# ESP32_BLE.net
KiCad netlist of a schematic drawn in Altium Designer
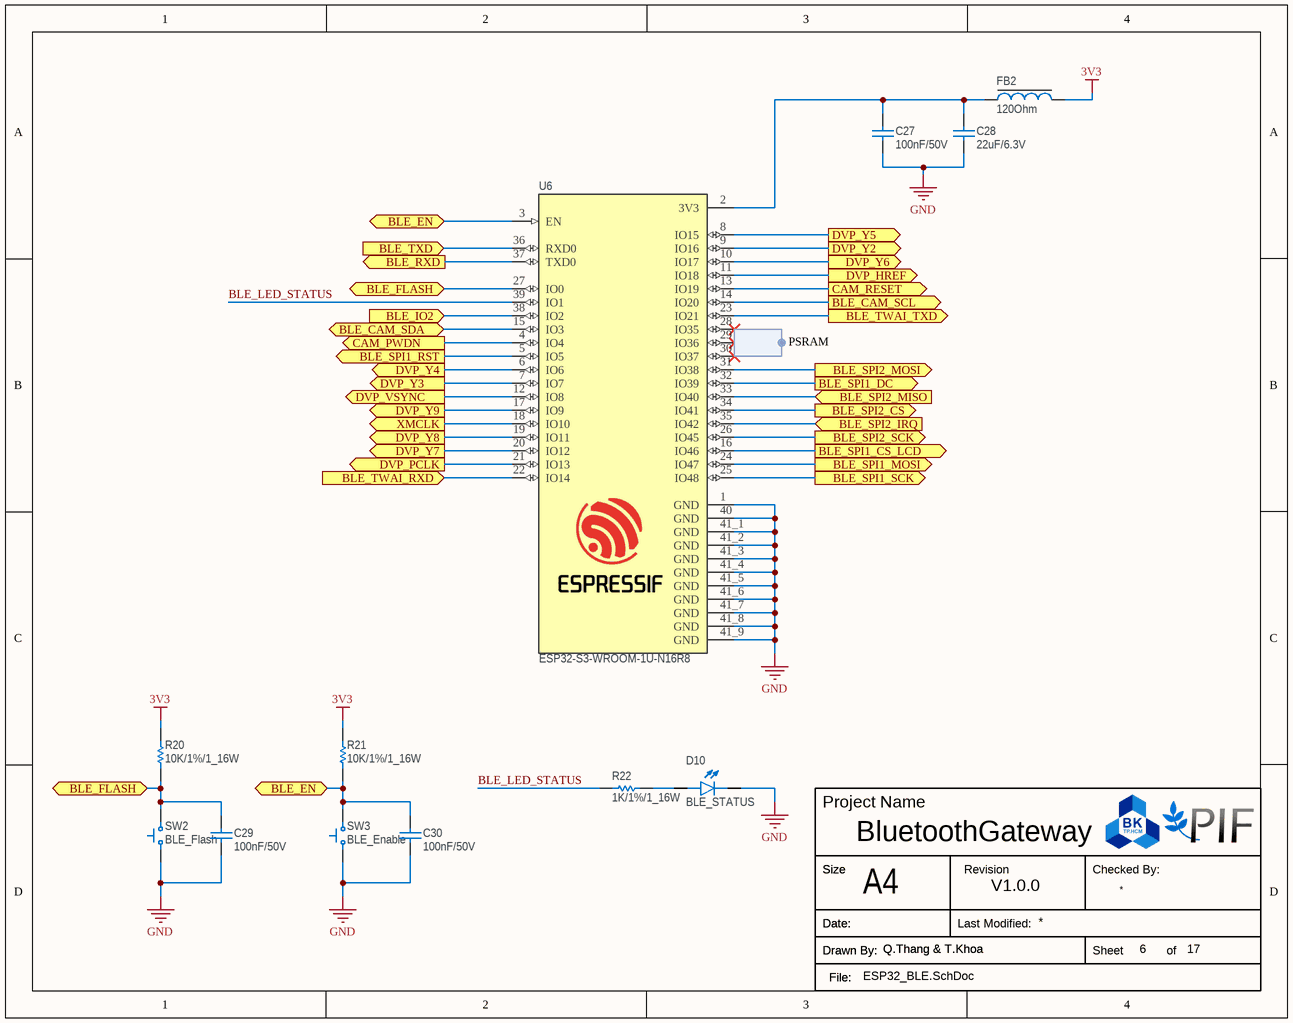
[diagram p0: ESP32_BLE.SchDoc]

(export (version "E")
  (design (tool "Eeschema 10.0.6"))
  (components
    (comp (ref "C27")
      (value "100nF/50V")
      (footprint "CAP_0805")
      (description "CAP, size 0805, 100nF, 50V")
      (fields (field (name "SUPPLY PART NUMBER") "Tụ Gốm 0805 100nF (0.1uF) 50V"))
      (libsource (lib "BluetoothTracking") (part "Ceramic_Cap_100nF_50V_0805"))
    )
    (comp (ref "C28")
      (value "22uF/6.3V")
      (footprint "CAP_0805")
      (description "CAP, size 0805, 22uF, 6.3V")
      (fields (field (name "SUPPLY PART NUMBER") "Tụ Gốm 0805 22uF 6.3V"))
      (libsource (lib "BluetoothTracking") (part "Ceramic_Cap_22uF_6.3V_0805"))
    )
    (comp (ref "C29")
      (value "100nF/50V")
      (footprint "CAP_0402")
      (description "CAP, size 0402, 100nF, 50V")
      (fields (field (name "SUPPLY PART NUMBER") "Tụ Gốm 0402 100nF (0.1uF) 50V"))
      (libsource (lib "BluetoothTracking") (part "Ceramic_Cap_100nF_50V_0402"))
    )
    (comp (ref "C30")
      (value "100nF/50V")
      (footprint "CAP_0402")
      (description "CAP, size 0402, 100nF, 50V")
      (fields (field (name "SUPPLY PART NUMBER") "Tụ Gốm 0402 100nF (0.1uF) 50V"))
      (libsource (lib "BluetoothTracking") (part "Ceramic_Cap_100nF_50V_0402"))
    )
    (comp (ref "D10")
      (value "BLE_STATUS")
      (footprint "LED_0603Y")
      (description "LED Yellow 0603")
      (fields (field (name "SUPPLY PART NUMBER") "LED Vàng 0603 Dán SMD Trong Suốt Harvatek"))
      (libsource (lib "BluetoothTracking") (part "LED_Yellow_0603"))
    )
    (comp (ref "FB2")
      (value "120Ohm")
      (footprint "Ferrite_Bead_0805")
      (description "Ferrite Bead, size 0805, 120Ohm, 2A")
      (fields (field (name "SUPPLY PART NUMBER") "CBW201209U121T Ferrite Beads 2A 120 Ohm 0805"))
      (libsource (lib "BluetoothTracking") (part "Ferrite_Bead_120Ohm_2A_0805"))
    )
    (comp (ref "R20")
      (value "10K/1%/1_16W")
      (footprint "RESISTOR_0402")
      (description "Resistor 0402 10KOhm 1% 1_16W")
      (fields (field (name "SUPPLY PART NUMBER") "Điện Trở 10 KOhm 0402 1%"))
      (libsource (lib "BluetoothTracking") (part "Res_10K_0402_1%"))
    )
    (comp (ref "R21")
      (value "10K/1%/1_16W")
      (footprint "RESISTOR_0402")
      (description "Resistor 0402 10KOhm 1% 1_16W")
      (fields (field (name "SUPPLY PART NUMBER") "Điện Trở 10 KOhm 0402 1%"))
      (libsource (lib "BluetoothTracking") (part "Res_10K_0402_1%"))
    )
    (comp (ref "R22")
      (value "1K/1%/1_16W")
      (footprint "RESISTOR_0402")
      (description "Resistor 0402 1KOhm 1% 1_16W")
      (fields (field (name "SUPPLY PART NUMBER") "Điện Trở 1 KOhm 0402 1%"))
      (libsource (lib "BluetoothTracking") (part "Res_1K_0402_1%"))
    )
    (comp (ref "SW2")
      (value "BLE_Flash")
      (footprint "Button_3x4mm_SMD_2P")
      (fields (field (name "SUPPLY PART NUMBER") "Nút Nhấn 3x4mm Cao 2.5mm 2 Chân SMD"))
      (libsource (lib "BluetoothTracking") (part "Button_SMD_3x4mm_2P"))
    )
    (comp (ref "SW3")
      (value "BLE_Enable")
      (footprint "Button_3x4mm_SMD_2P")
      (fields (field (name "SUPPLY PART NUMBER") "Nút Nhấn 3x4mm Cao 2.5mm 2 Chân SMD"))
      (libsource (lib "BluetoothTracking") (part "Button_SMD_3x4mm_2P"))
    )
    (comp (ref "U6")
      (value "ESP32-S3-WROOM-1U-N16R8")
      (footprint "XCVR_ESP32-S3-WROOM-1U-N16R8")
      (fields (field (name "SUPPLY PART NUMBER") "ESP32-S3-WROOM-1U-N16R8 Thu Phát Wifi BLE ESP32 16MB"))
      (libsource (lib "BluetoothTracking") (part "ESP32-S3-WROOM-1U-N16R8"))
    )
  )
  (nets
    (net (code "1") (name "/BLE_CAM_SCL") (class "Default")
      (node (ref "U6") (pin "14") (pinfunction "IO20_14") (pintype "bidirectional"))
    )
    (net (code "2") (name "/BLE_CAM_SDA") (class "Default")
      (node (ref "U6") (pin "15") (pinfunction "IO3_15") (pintype "bidirectional"))
    )
    (net (code "3") (name "/BLE_EN") (class "Default")
      (node (ref "C30") (pin "2") (pinfunction "2_2") (pintype "passive"))
      (node (ref "R21") (pin "1") (pinfunction "1_1") (pintype "passive"))
      (node (ref "SW3") (pin "2") (pinfunction "2_2") (pintype "passive"))
      (node (ref "U6") (pin "3") (pinfunction "EN_3") (pintype "input"))
    )
    (net (code "4") (name "/BLE_FLASH") (class "Default")
      (node (ref "C29") (pin "2") (pinfunction "2_2") (pintype "passive"))
      (node (ref "R20") (pin "1") (pinfunction "1_1") (pintype "passive"))
      (node (ref "SW2") (pin "2") (pinfunction "2_2") (pintype "passive"))
      (node (ref "U6") (pin "27") (pinfunction "IO0_27") (pintype "bidirectional"))
    )
    (net (code "5") (name "/BLE_IO2") (class "Default")
      (node (ref "U6") (pin "38") (pinfunction "IO2_38") (pintype "bidirectional"))
    )
    (net (code "6") (name "/BLE_LED_STATUS") (class "Default")
      (node (ref "R22") (pin "1") (pinfunction "1_1") (pintype "passive"))
      (node (ref "U6") (pin "39") (pinfunction "IO1_39") (pintype "bidirectional"))
    )
    (net (code "7") (name "/BLE_RXD") (class "Default")
      (node (ref "U6") (pin "37") (pinfunction "TXD0_37") (pintype "bidirectional"))
    )
    (net (code "8") (name "/BLE_SPI1_CS_LCD") (class "Default")
      (node (ref "U6") (pin "16") (pinfunction "IO46_16") (pintype "bidirectional"))
    )
    (net (code "9") (name "/BLE_SPI1_DC") (class "Default")
      (node (ref "U6") (pin "32") (pinfunction "IO39_32") (pintype "bidirectional"))
    )
    (net (code "10") (name "/BLE_SPI1_MOSI") (class "Default")
      (node (ref "U6") (pin "24") (pinfunction "IO47_24") (pintype "bidirectional"))
    )
    (net (code "11") (name "/BLE_SPI1_RST") (class "Default")
      (node (ref "U6") (pin "5") (pinfunction "IO5_5") (pintype "bidirectional"))
    )
    (net (code "12") (name "/BLE_SPI1_SCK") (class "Default")
      (node (ref "U6") (pin "25") (pinfunction "IO48_25") (pintype "bidirectional"))
    )
    (net (code "13") (name "/BLE_SPI2_CS") (class "Default")
      (node (ref "U6") (pin "34") (pinfunction "IO41_34") (pintype "bidirectional"))
    )
    (net (code "14") (name "/BLE_SPI2_IRQ") (class "Default")
      (node (ref "U6") (pin "35") (pinfunction "IO42_35") (pintype "bidirectional"))
    )
    (net (code "15") (name "/BLE_SPI2_MISO") (class "Default")
      (node (ref "U6") (pin "33") (pinfunction "IO40_33") (pintype "bidirectional"))
    )
    (net (code "16") (name "/BLE_SPI2_MOSI") (class "Default")
      (node (ref "U6") (pin "31") (pinfunction "IO38_31") (pintype "bidirectional"))
    )
    (net (code "17") (name "/BLE_SPI2_SCK") (class "Default")
      (node (ref "U6") (pin "26") (pinfunction "IO45_26") (pintype "bidirectional"))
    )
    (net (code "18") (name "/BLE_TWAI_RXD") (class "Default")
      (node (ref "U6") (pin "22") (pinfunction "IO14_22") (pintype "bidirectional"))
    )
    (net (code "19") (name "/BLE_TWAI_TXD") (class "Default")
      (node (ref "U6") (pin "23") (pinfunction "IO21_23") (pintype "bidirectional"))
    )
    (net (code "20") (name "/BLE_TXD") (class "Default")
      (node (ref "U6") (pin "36") (pinfunction "RXD0_36") (pintype "bidirectional"))
    )
    (net (code "21") (name "/CAM_PWDN") (class "Default")
      (node (ref "U6") (pin "4") (pinfunction "IO4_4") (pintype "bidirectional"))
    )
    (net (code "22") (name "/CAM_RESET") (class "Default")
      (node (ref "U6") (pin "13") (pinfunction "IO19_13") (pintype "bidirectional"))
    )
    (net (code "23") (name "/DVP_HREF") (class "Default")
      (node (ref "U6") (pin "11") (pinfunction "IO18_11") (pintype "bidirectional"))
    )
    (net (code "24") (name "/DVP_PCLK") (class "Default")
      (node (ref "U6") (pin "21") (pinfunction "IO13_21") (pintype "bidirectional"))
    )
    (net (code "25") (name "/DVP_VSYNC") (class "Default")
      (node (ref "U6") (pin "12") (pinfunction "IO8_12") (pintype "bidirectional"))
    )
    (net (code "26") (name "/DVP_Y2") (class "Default")
      (node (ref "U6") (pin "9") (pinfunction "IO16_9") (pintype "bidirectional"))
    )
    (net (code "27") (name "/DVP_Y3") (class "Default")
      (node (ref "U6") (pin "7") (pinfunction "IO7_7") (pintype "bidirectional"))
    )
    (net (code "28") (name "/DVP_Y4") (class "Default")
      (node (ref "U6") (pin "6") (pinfunction "IO6_6") (pintype "bidirectional"))
    )
    (net (code "29") (name "/DVP_Y5") (class "Default")
      (node (ref "U6") (pin "8") (pinfunction "IO15_8") (pintype "bidirectional"))
    )
    (net (code "30") (name "/DVP_Y6") (class "Default")
      (node (ref "U6") (pin "10") (pinfunction "IO17_10") (pintype "bidirectional"))
    )
    (net (code "31") (name "/DVP_Y7") (class "Default")
      (node (ref "U6") (pin "20") (pinfunction "IO12_20") (pintype "bidirectional"))
    )
    (net (code "32") (name "/DVP_Y8") (class "Default")
      (node (ref "U6") (pin "19") (pinfunction "IO11_19") (pintype "bidirectional"))
    )
    (net (code "33") (name "/DVP_Y9") (class "Default")
      (node (ref "U6") (pin "17") (pinfunction "IO9_17") (pintype "bidirectional"))
    )
    (net (code "34") (name "/XMCLK") (class "Default")
      (node (ref "U6") (pin "18") (pinfunction "IO10_18") (pintype "bidirectional"))
    )
    (net (code "35") (name "3V3") (class "Default")
      (node (ref "FB2") (pin "2") (pinfunction "2_2") (pintype "passive"))
      (node (ref "R20") (pin "2") (pinfunction "2_2") (pintype "passive"))
      (node (ref "R21") (pin "2") (pinfunction "2_2") (pintype "passive"))
    )
    (net (code "36") (name "GND") (class "Default")
      (node (ref "C27") (pin "1") (pinfunction "1_1") (pintype "passive"))
      (node (ref "C28") (pin "1") (pinfunction "1_1") (pintype "passive"))
      (node (ref "C29") (pin "1") (pinfunction "1_1") (pintype "passive"))
      (node (ref "C30") (pin "1") (pinfunction "1_1") (pintype "passive"))
      (node (ref "D10") (pin "C") (pinfunction "C_C") (pintype "passive"))
      (node (ref "SW2") (pin "1") (pinfunction "1_1") (pintype "passive"))
      (node (ref "SW3") (pin "1") (pinfunction "1_1") (pintype "passive"))
      (node (ref "U6") (pin "1") (pinfunction "GND_1") (pintype "power_in"))
      (node (ref "U6") (pin "40") (pinfunction "GND_40") (pintype "power_in"))
      (node (ref "U6") (pin "41_1") (pinfunction "GND_41_1") (pintype "power_in"))
      (node (ref "U6") (pin "41_2") (pinfunction "GND_41_2") (pintype "power_in"))
      (node (ref "U6") (pin "41_3") (pinfunction "GND_41_3") (pintype "power_in"))
      (node (ref "U6") (pin "41_4") (pinfunction "GND_41_4") (pintype "power_in"))
      (node (ref "U6") (pin "41_5") (pinfunction "GND_41_5") (pintype "power_in"))
      (node (ref "U6") (pin "41_6") (pinfunction "GND_41_6") (pintype "power_in"))
      (node (ref "U6") (pin "41_7") (pinfunction "GND_41_7") (pintype "power_in"))
      (node (ref "U6") (pin "41_8") (pinfunction "GND_41_8") (pintype "power_in"))
      (node (ref "U6") (pin "41_9") (pinfunction "GND_41_9") (pintype "power_in"))
    )
    (net (code "37") (name "Net-(D10-PadA)") (class "Default")
      (node (ref "D10") (pin "A") (pinfunction "A_A") (pintype "passive"))
      (node (ref "R22") (pin "2") (pinfunction "2_2") (pintype "passive"))
    )
    (net (code "38") (name "Net-(U6-3V3)") (class "Default")
      (node (ref "C27") (pin "2") (pinfunction "2_2") (pintype "passive"))
      (node (ref "C28") (pin "2") (pinfunction "2_2") (pintype "passive"))
      (node (ref "FB2") (pin "1") (pinfunction "1_1") (pintype "passive"))
      (node (ref "U6") (pin "2") (pinfunction "3V3_2") (pintype "power_in"))
    )
    (net (code "39") (name "unconnected-(U6-IO35-Pad28)") (class "Default")
      (node (ref "U6") (pin "28") (pinfunction "IO35_28") (pintype "bidirectional+no_connect"))
    )
    (net (code "40") (name "unconnected-(U6-IO36-Pad29)") (class "Default")
      (node (ref "U6") (pin "29") (pinfunction "IO36_29") (pintype "bidirectional+no_connect"))
    )
    (net (code "41") (name "unconnected-(U6-IO37-Pad30)") (class "Default")
      (node (ref "U6") (pin "30") (pinfunction "IO37_30") (pintype "bidirectional+no_connect"))
    )
  )
)
